# ESP32_PD.net
KiCad netlist of a schematic drawn in Altium Designer
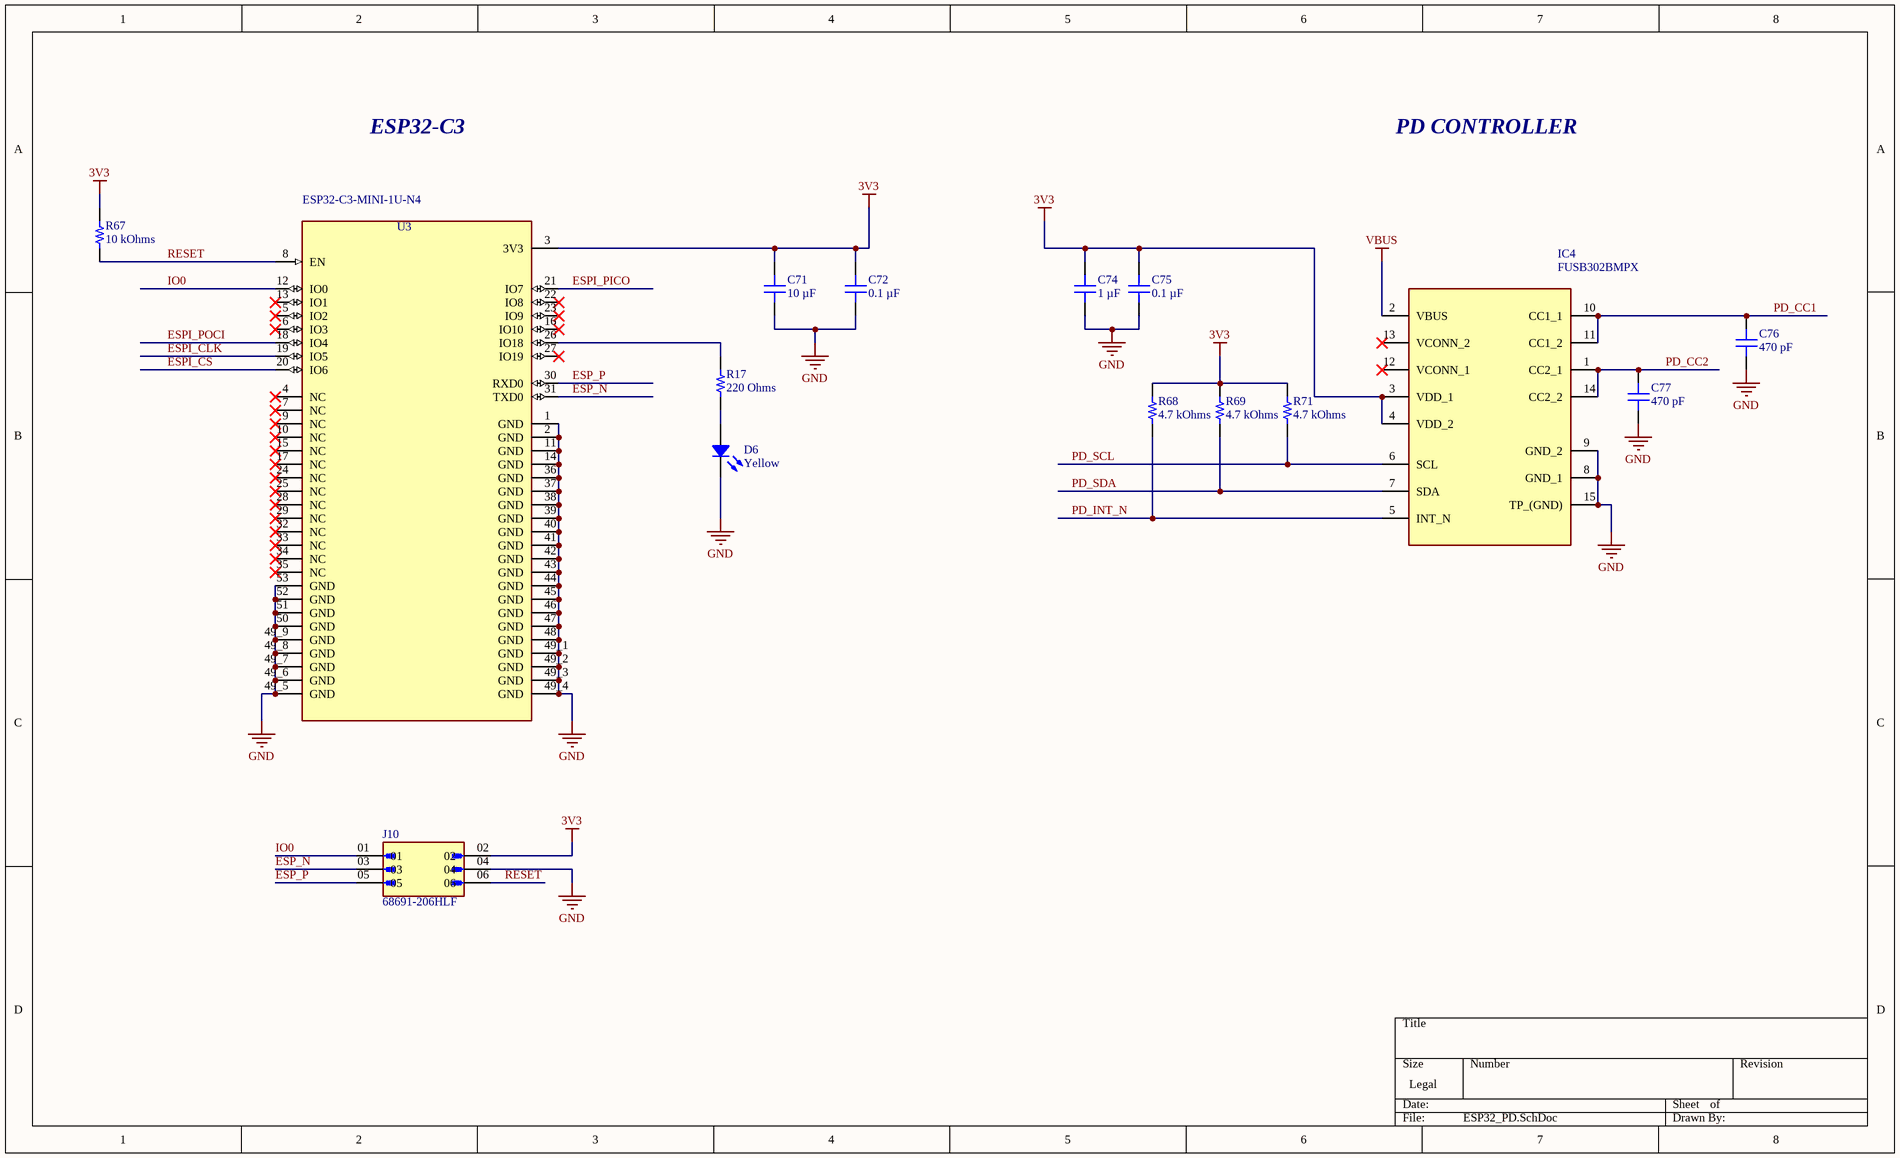
[diagram p0: ESP32_PD.SchDoc]

(export (version "E")
  (design (tool "Eeschema 10.0.6"))
  (components
    (comp (ref "C71")
      (value "10 µF")
      (footprint "CAP 0603_1608")
      (description "CAP CER 10UF 6.3V X5R 0603")
      (fields
        (field (name "PART NUMBER") "GRM188R60J106ME47D")
        (field (name "MANUFACTURER") "Murata Electronics")
      )
      (libsource (lib "Celestial Altium Library - altium_library") (part "Capacitor"))
    )
    (comp (ref "C72")
      (value "0.1 µF")
      (footprint "CAP 0603_1608")
      (description "CAP CER 0.1UF 6.3V X7R 0603")
      (fields
        (field (name "PART NUMBER") "6R3X14W104MV4T")
        (field (name "MANUFACTURER") "Johanson Dielectrics Inc.")
      )
      (libsource (lib "Celestial Altium Library - altium_library") (part "Capacitor"))
    )
    (comp (ref "C74")
      (value "1 µF")
      (footprint "CAP 0603_1608")
      (description "CAP CER 1UF 16V X7R 0603")
      (fields (field (name "PART NUMBER") "C0603C105K4RACAUTO") (field (name "MANUFACTURER") "KEMET"))
      (libsource (lib "Celestial Altium Library - altium_library") (part "Capacitor"))
    )
    (comp (ref "C75")
      (value "0.1 µF")
      (footprint "CAP 0402_1005")
      (description "CAP CER 0402 0.1UF 16V X7R 10%")
      (fields (field (name "PART NUMBER") "C0402C104K4RECAUTO") (field (name "MANUFACTURER") "KEMET"))
      (libsource (lib "Celestial Altium Library - altium_library") (part "Capacitor"))
    )
    (comp (ref "C76")
      (value "470 pF")
      (footprint "CAP 0402_1005")
      (description "CAP CER 470PF 50V C0G/NP0 0402")
      (fields (field (name "PART NUMBER") "C0402C471J5GACAUTO") (field (name "MANUFACTURER") "KEMET"))
      (libsource (lib "Celestial Altium Library - altium_library") (part "Capacitor"))
    )
    (comp (ref "C77")
      (value "470 pF")
      (footprint "CAP 0402_1005")
      (description "CAP CER 470PF 50V C0G/NP0 0402")
      (fields (field (name "PART NUMBER") "C0402C471J5GACAUTO") (field (name "MANUFACTURER") "KEMET"))
      (libsource (lib "Celestial Altium Library - altium_library") (part "Capacitor"))
    )
    (comp (ref "D6")
      (value "Yellow")
      (footprint "LED 0603_1608 YELLOW")
      (description "LED YELLOW DIFFUSED SMD")
      (fields
        (field (name "PART NUMBER") "SML-LX0603YW-TR")
        (field (name "MANUFACTURER") "Lumex Opto/Components Inc.")
      )
      (libsource (lib "Celestial Altium Library - altium_library") (part "LED"))
    )
    (comp (ref "IC4")
      (value "FUSB302BMPX")
      (footprint "SamacSys:QFN50P250X250X80-15N")
      (description "Integrated Circuit")
      (fields (field (name "MOUSER PART NUMBER") "512-FUSB302BMPX"))
      (libsource (lib "SamacSys") (part "FUSB302BMPX"))
    )
    (comp (ref "J10")
      (value "68691-206HLF")
      (footprint "AMPHENOL_68691-206HLF:AMPHENOL_68691-206HLF")
      (description "Connector Header Through Hole 6 position 0.100 (2.54mm)")
      (fields (field (name "MF") "FCI"))
      (libsource (lib "68691-206HLF") (part "68691-206HLF"))
    )
    (comp (ref "R17")
      (value "220 Ohms")
      (footprint "RES 0402_1005")
      (description "RES 220 OHM 1% 1/16W 0402")
      (fields (field (name "PART NUMBER") "RC0402FR-07220RL") (field (name "MANUFACTURER") "Yageo"))
      (libsource (lib "Celestial Altium Library - altium_library") (part "Resistor"))
    )
    (comp (ref "R67")
      (value "10 kOhms")
      (footprint "RES 0402_1005")
      (description "RES 10K OHM 0.1% 1/10W 0402")
      (fields
        (field (name "PART NUMBER") "RP73PF1E10KBTD")
        (field (name "MANUFACTURER") "TE Connectivity Passive Product")
      )
      (libsource (lib "Celestial Altium Library - altium_library") (part "Resistor"))
    )
    (comp (ref "R68")
      (value "4.7 kOhms")
      (footprint "RES 0402_1005")
      (description "RES SMD 4.7K OHM 1% 1/16W 0402")
      (fields (field (name "PART NUMBER") "RT0402FRE074K7L") (field (name "MANUFACTURER") "Yageo"))
      (libsource (lib "Celestial Altium Library - altium_library") (part "Resistor"))
    )
    (comp (ref "R69")
      (value "4.7 kOhms")
      (footprint "RES 0402_1005")
      (description "RES SMD 4.7K OHM 1% 1/16W 0402")
      (fields (field (name "PART NUMBER") "RT0402FRE074K7L") (field (name "MANUFACTURER") "Yageo"))
      (libsource (lib "Celestial Altium Library - altium_library") (part "Resistor"))
    )
    (comp (ref "R71")
      (value "4.7 kOhms")
      (footprint "RES 0402_1005")
      (description "RES SMD 4.7K OHM 1% 1/16W 0402")
      (fields (field (name "PART NUMBER") "RT0402FRE074K7L") (field (name "MANUFACTURER") "Yageo"))
      (libsource (lib "Celestial Altium Library - altium_library") (part "Resistor"))
    )
    (comp (ref "U3")
      (value "ESP32-C3-MINI-1U-N4")
      (footprint "XCVR_ESP32-C3-MINI-1U-N4:XCVR_ESP32-C3-MINI-1U-N4")
      (fields
        (field (name "MF") "Espressif Systems")
        (field (name "DIGI-KEY_PART_NUMBER") "1965-ESP32-C3-MINI-1U-N4TR-ND")
      )
      (libsource (lib "ESP32-C3-MINI-1U-N4") (part "ESP32-C3-MINI-1U-N4"))
    )
  )
  (nets
    (net (code "1") (name "/ESPI_CLK") (class "Default")
      (node (ref "U3") (pin "19") (pinfunction "IO5_19") (pintype "bidirectional"))
    )
    (net (code "2") (name "/ESPI_CS") (class "Default")
      (node (ref "U3") (pin "20") (pinfunction "IO6_20") (pintype "bidirectional"))
    )
    (net (code "3") (name "/ESPI_PICO") (class "Default")
      (node (ref "U3") (pin "21") (pinfunction "IO7_21") (pintype "bidirectional"))
    )
    (net (code "4") (name "/ESPI_POCI") (class "Default")
      (node (ref "U3") (pin "18") (pinfunction "IO4_18") (pintype "bidirectional"))
    )
    (net (code "5") (name "/ESP_N") (class "Default")
      (node (ref "J10") (pin "03") (pinfunction "03_03") (pintype "passive"))
      (node (ref "U3") (pin "31") (pinfunction "TXD0_31") (pintype "bidirectional"))
    )
    (net (code "6") (name "/ESP_P") (class "Default")
      (node (ref "J10") (pin "05") (pinfunction "05_05") (pintype "passive"))
      (node (ref "U3") (pin "30") (pinfunction "RXD0_30") (pintype "bidirectional"))
    )
    (net (code "7") (name "/IO0") (class "Default")
      (node (ref "J10") (pin "01") (pinfunction "01_01") (pintype "passive"))
      (node (ref "U3") (pin "12") (pinfunction "IO0_12") (pintype "bidirectional"))
    )
    (net (code "8") (name "/PD_CC1") (class "Default")
      (node (ref "C76") (pin "2") (pinfunction "2_2") (pintype "passive"))
      (node (ref "IC4") (pin "10") (pinfunction "CC1_1_10") (pintype "passive"))
      (node (ref "IC4") (pin "11") (pinfunction "CC1_2_11") (pintype "passive"))
    )
    (net (code "9") (name "/PD_CC2") (class "Default")
      (node (ref "C77") (pin "2") (pinfunction "2_2") (pintype "passive"))
      (node (ref "IC4") (pin "1") (pinfunction "CC2_1_1") (pintype "passive"))
      (node (ref "IC4") (pin "14") (pinfunction "CC2_2_14") (pintype "passive"))
    )
    (net (code "10") (name "/PD_INT_N") (class "Default")
      (node (ref "IC4") (pin "5") (pinfunction "INT_N_5") (pintype "passive"))
      (node (ref "R68") (pin "1") (pinfunction "1_1") (pintype "passive"))
    )
    (net (code "11") (name "/PD_SCL") (class "Default")
      (node (ref "IC4") (pin "6") (pinfunction "SCL_6") (pintype "passive"))
      (node (ref "R71") (pin "1") (pinfunction "1_1") (pintype "passive"))
    )
    (net (code "12") (name "/PD_SDA") (class "Default")
      (node (ref "IC4") (pin "7") (pinfunction "SDA_7") (pintype "passive"))
      (node (ref "R69") (pin "1") (pinfunction "1_1") (pintype "passive"))
    )
    (net (code "13") (name "/RESET") (class "Default")
      (node (ref "J10") (pin "06") (pinfunction "06_06") (pintype "passive"))
      (node (ref "R67") (pin "1") (pinfunction "1_1") (pintype "passive"))
      (node (ref "U3") (pin "8") (pinfunction "EN_8") (pintype "input"))
    )
    (net (code "14") (name "3V3") (class "Default")
      (node (ref "C71") (pin "2") (pinfunction "2_2") (pintype "passive"))
      (node (ref "C72") (pin "2") (pinfunction "2_2") (pintype "passive"))
      (node (ref "C74") (pin "2") (pinfunction "2_2") (pintype "passive"))
      (node (ref "C75") (pin "2") (pinfunction "2_2") (pintype "passive"))
      (node (ref "IC4") (pin "3") (pinfunction "VDD_1_3") (pintype "passive"))
      (node (ref "IC4") (pin "4") (pinfunction "VDD_2_4") (pintype "passive"))
      (node (ref "J10") (pin "02") (pinfunction "02_02") (pintype "passive"))
      (node (ref "R67") (pin "2") (pinfunction "2_2") (pintype "passive"))
      (node (ref "R68") (pin "2") (pinfunction "2_2") (pintype "passive"))
      (node (ref "R69") (pin "2") (pinfunction "2_2") (pintype "passive"))
      (node (ref "R71") (pin "2") (pinfunction "2_2") (pintype "passive"))
      (node (ref "U3") (pin "3") (pinfunction "3V3_3") (pintype "power_in"))
    )
    (net (code "15") (name "GND") (class "Default")
      (node (ref "C71") (pin "1") (pinfunction "1_1") (pintype "passive"))
      (node (ref "C72") (pin "1") (pinfunction "1_1") (pintype "passive"))
      (node (ref "C74") (pin "1") (pinfunction "1_1") (pintype "passive"))
      (node (ref "C75") (pin "1") (pinfunction "1_1") (pintype "passive"))
      (node (ref "C76") (pin "1") (pinfunction "1_1") (pintype "passive"))
      (node (ref "C77") (pin "1") (pinfunction "1_1") (pintype "passive"))
      (node (ref "D6") (pin "2") (pinfunction "2_2") (pintype "passive"))
      (node (ref "IC4") (pin "15") (pinfunction "TP_(GND)_15") (pintype "passive"))
      (node (ref "IC4") (pin "8") (pinfunction "GND_1_8") (pintype "passive"))
      (node (ref "IC4") (pin "9") (pinfunction "GND_2_9") (pintype "passive"))
      (node (ref "J10") (pin "04") (pinfunction "04_04") (pintype "passive"))
      (node (ref "U3") (pin "1") (pinfunction "GND_1") (pintype "power_in"))
      (node (ref "U3") (pin "11") (pinfunction "GND_11") (pintype "power_in"))
      (node (ref "U3") (pin "14") (pinfunction "GND_14") (pintype "power_in"))
      (node (ref "U3") (pin "2") (pinfunction "GND_2") (pintype "power_in"))
      (node (ref "U3") (pin "36") (pinfunction "GND_36") (pintype "power_in"))
      (node (ref "U3") (pin "37") (pinfunction "GND_37") (pintype "power_in"))
      (node (ref "U3") (pin "38") (pinfunction "GND_38") (pintype "power_in"))
      (node (ref "U3") (pin "39") (pinfunction "GND_39") (pintype "power_in"))
      (node (ref "U3") (pin "40") (pinfunction "GND_40") (pintype "power_in"))
      (node (ref "U3") (pin "41") (pinfunction "GND_41") (pintype "power_in"))
      (node (ref "U3") (pin "42") (pinfunction "GND_42") (pintype "power_in"))
      (node (ref "U3") (pin "43") (pinfunction "GND_43") (pintype "power_in"))
      (node (ref "U3") (pin "44") (pinfunction "GND_44") (pintype "power_in"))
      (node (ref "U3") (pin "45") (pinfunction "GND_45") (pintype "power_in"))
      (node (ref "U3") (pin "46") (pinfunction "GND_46") (pintype "power_in"))
      (node (ref "U3") (pin "47") (pinfunction "GND_47") (pintype "power_in"))
      (node (ref "U3") (pin "48") (pinfunction "GND_48") (pintype "power_in"))
      (node (ref "U3") (pin "49_1") (pinfunction "GND_49_1") (pintype "power_in"))
      (node (ref "U3") (pin "49_2") (pinfunction "GND_49_2") (pintype "power_in"))
      (node (ref "U3") (pin "49_3") (pinfunction "GND_49_3") (pintype "power_in"))
      (node (ref "U3") (pin "49_4") (pinfunction "GND_49_4") (pintype "power_in"))
      (node (ref "U3") (pin "49_5") (pinfunction "GND_49_5") (pintype "power_in"))
      (node (ref "U3") (pin "49_6") (pinfunction "GND_49_6") (pintype "power_in"))
      (node (ref "U3") (pin "49_7") (pinfunction "GND_49_7") (pintype "power_in"))
      (node (ref "U3") (pin "49_8") (pinfunction "GND_49_8") (pintype "power_in"))
      (node (ref "U3") (pin "49_9") (pinfunction "GND_49_9") (pintype "power_in"))
      (node (ref "U3") (pin "50") (pinfunction "GND_50") (pintype "power_in"))
      (node (ref "U3") (pin "51") (pinfunction "GND_51") (pintype "power_in"))
      (node (ref "U3") (pin "52") (pinfunction "GND_52") (pintype "power_in"))
      (node (ref "U3") (pin "53") (pinfunction "GND_53") (pintype "power_in"))
    )
    (net (code "16") (name "Net-(D6-Pad1)") (class "Default")
      (node (ref "D6") (pin "1") (pinfunction "1_1") (pintype "passive"))
      (node (ref "R17") (pin "2") (pinfunction "2_2") (pintype "passive"))
    )
    (net (code "17") (name "Net-(U3-IO18)") (class "Default")
      (node (ref "R17") (pin "1") (pinfunction "1_1") (pintype "passive"))
      (node (ref "U3") (pin "26") (pinfunction "IO18_26") (pintype "bidirectional"))
    )
    (net (code "18") (name "VBUS") (class "Default")
      (node (ref "IC4") (pin "2") (pinfunction "VBUS_2") (pintype "passive"))
    )
    (net (code "19") (name "unconnected-(IC4-VCONN_1-Pad12)") (class "Default")
      (node (ref "IC4") (pin "12") (pinfunction "VCONN_1_12") (pintype "passive+no_connect"))
    )
    (net (code "20") (name "unconnected-(IC4-VCONN_2-Pad13)") (class "Default")
      (node (ref "IC4") (pin "13") (pinfunction "VCONN_2_13") (pintype "passive+no_connect"))
    )
    (net (code "21") (name "unconnected-(U3-IO1-Pad13)") (class "Default")
      (node (ref "U3") (pin "13") (pinfunction "IO1_13") (pintype "bidirectional+no_connect"))
    )
    (net (code "22") (name "unconnected-(U3-IO2-Pad5)") (class "Default")
      (node (ref "U3") (pin "5") (pinfunction "IO2_5") (pintype "bidirectional+no_connect"))
    )
    (net (code "23") (name "unconnected-(U3-IO3-Pad6)") (class "Default")
      (node (ref "U3") (pin "6") (pinfunction "IO3_6") (pintype "bidirectional+no_connect"))
    )
    (net (code "24") (name "unconnected-(U3-IO8-Pad22)") (class "Default")
      (node (ref "U3") (pin "22") (pinfunction "IO8_22") (pintype "bidirectional+no_connect"))
    )
    (net (code "25") (name "unconnected-(U3-IO9-Pad23)") (class "Default")
      (node (ref "U3") (pin "23") (pinfunction "IO9_23") (pintype "bidirectional+no_connect"))
    )
    (net (code "26") (name "unconnected-(U3-IO10-Pad16)") (class "Default")
      (node (ref "U3") (pin "16") (pinfunction "IO10_16") (pintype "bidirectional+no_connect"))
    )
    (net (code "27") (name "unconnected-(U3-IO19-Pad27)") (class "Default")
      (node (ref "U3") (pin "27") (pinfunction "IO19_27") (pintype "bidirectional+no_connect"))
    )
    (net (code "28") (name "unconnected-(U3-NC-Pad4)") (class "Default")
      (node (ref "U3") (pin "4") (pinfunction "NC_4") (pintype "passive+no_connect"))
    )
    (net (code "29") (name "unconnected-(U3-NC-Pad7)") (class "Default")
      (node (ref "U3") (pin "7") (pinfunction "NC_7") (pintype "passive+no_connect"))
    )
    (net (code "30") (name "unconnected-(U3-NC-Pad9)") (class "Default")
      (node (ref "U3") (pin "9") (pinfunction "NC_9") (pintype "passive+no_connect"))
    )
    (net (code "31") (name "unconnected-(U3-NC-Pad10)") (class "Default")
      (node (ref "U3") (pin "10") (pinfunction "NC_10") (pintype "passive+no_connect"))
    )
    (net (code "32") (name "unconnected-(U3-NC-Pad15)") (class "Default")
      (node (ref "U3") (pin "15") (pinfunction "NC_15") (pintype "passive+no_connect"))
    )
    (net (code "33") (name "unconnected-(U3-NC-Pad17)") (class "Default")
      (node (ref "U3") (pin "17") (pinfunction "NC_17") (pintype "passive+no_connect"))
    )
    (net (code "34") (name "unconnected-(U3-NC-Pad24)") (class "Default")
      (node (ref "U3") (pin "24") (pinfunction "NC_24") (pintype "passive+no_connect"))
    )
    (net (code "35") (name "unconnected-(U3-NC-Pad25)") (class "Default")
      (node (ref "U3") (pin "25") (pinfunction "NC_25") (pintype "passive+no_connect"))
    )
    (net (code "36") (name "unconnected-(U3-NC-Pad28)") (class "Default")
      (node (ref "U3") (pin "28") (pinfunction "NC_28") (pintype "passive+no_connect"))
    )
    (net (code "37") (name "unconnected-(U3-NC-Pad29)") (class "Default")
      (node (ref "U3") (pin "29") (pinfunction "NC_29") (pintype "passive+no_connect"))
    )
    (net (code "38") (name "unconnected-(U3-NC-Pad32)") (class "Default")
      (node (ref "U3") (pin "32") (pinfunction "NC_32") (pintype "passive+no_connect"))
    )
    (net (code "39") (name "unconnected-(U3-NC-Pad33)") (class "Default")
      (node (ref "U3") (pin "33") (pinfunction "NC_33") (pintype "passive+no_connect"))
    )
    (net (code "40") (name "unconnected-(U3-NC-Pad34)") (class "Default")
      (node (ref "U3") (pin "34") (pinfunction "NC_34") (pintype "passive+no_connect"))
    )
    (net (code "41") (name "unconnected-(U3-NC-Pad35)") (class "Default")
      (node (ref "U3") (pin "35") (pinfunction "NC_35") (pintype "passive+no_connect"))
    )
  )
)
